# B21DCDT245_05.net
KiCad netlist of a schematic drawn in Altium Designer
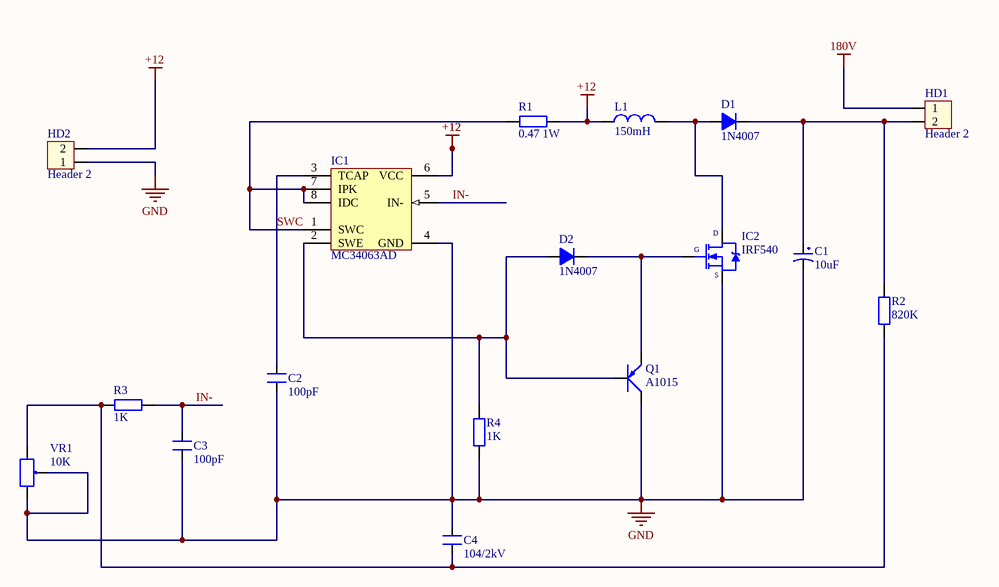
[diagram p0: B21DCDT245_05.SchDoc]

(export (version "E")
  (design (tool "Eeschema 10.0.6"))
  (components
    (comp (ref "C1")
      (value "10uF")
      (footprint "CP1/2")
      (description "Cap P  0,1uF < 22uF , 16 - 50V")
      (libsource (lib "Devzone_SCHLib") (part "CP1"))
    )
    (comp (ref "C2")
      (value "100pF")
      (footprint "CN1")
      (description "Cap np  1pF - 472pF")
      (libsource (lib "syhaunguyen") (part "CN1"))
    )
    (comp (ref "C3")
      (value "100pF")
      (footprint "CN1")
      (description "Cap np  1pF - 472pF")
      (libsource (lib "syhaunguyen") (part "CN1"))
    )
    (comp (ref "C4")
      (value "104/2kV")
      (footprint "CN1")
      (description "Cap np  1pF - 472pF")
      (libsource (lib "syhaunguyen") (part "CN1"))
    )
    (comp (ref "D1")
      (value "1N4007")
      (footprint "D1A")
      (description "Diode 1A")
      (libsource (lib "syhaunguyen") (part "D1A"))
    )
    (comp (ref "D2")
      (value "1N4007")
      (footprint "D1A")
      (description "Diode 1A")
      (libsource (lib "syhaunguyen") (part "D1A"))
    )
    (comp (ref "HD1")
      (value "Header 2")
      (footprint "HED2")
      (description "Header 2 (Green)")
      (libsource (lib "") (part "Hed2_1"))
    )
    (comp (ref "HD2")
      (value "Header 2")
      (footprint "HED2")
      (description "Header 2 (Green)")
      (libsource (lib "Devzone_SCHLib") (part "Hed2"))
    )
    (comp (ref "IC1")
      (value "MC34063AD")
      (footprint "DIP8")
      (description "DC-to-DC Converter Control Circuit")
      (fields (field (name "PUBLISHER") "Altium Limited"))
      (libsource (lib "Devzone_SCHLib") (part "MC34063AD"))
    )
    (comp (ref "IC2")
      (value "IRF540")
      (footprint "QTO220 - FLAT")
      (libsource (lib "My library altium") (part "IRF540"))
    )
    (comp (ref "L1")
      (value "150mH")
      (footprint "L/0.4")
      (description "Inductor")
      (libsource (lib "syhaunguyen") (part "L1"))
    )
    (comp (ref "Q1")
      (value "A1015")
      (footprint "QTO-92")
      (description "PNP 600mW, ECB")
      (libsource (lib "Devzone_SCHLib") (part "A1015"))
    )
    (comp (ref "R1")
      (value "0.47 1W")
      (footprint "VioletofSun:SM-1206")
      (description "Resistor SMD")
      (libsource (lib "VioletofSun") (part "RM"))
    )
    (comp (ref "R2")
      (value "820K")
      (footprint "VioletofSun:SM-1206")
      (description "Resistor SMD")
      (libsource (lib "VioletofSun") (part "RM"))
    )
    (comp (ref "R3")
      (value "1K")
      (footprint "VioletofSun:SM-1206")
      (description "Resistor SMD")
      (libsource (lib "VioletofSun") (part "RM"))
    )
    (comp (ref "R4")
      (value "1K")
      (footprint "VioletofSun:SM-1206")
      (description "Resistor SMD")
      (libsource (lib "VioletofSun") (part "RM"))
    )
    (comp (ref "VR1")
      (value "10K")
      (footprint "VR")
      (description "Var Resistor")
      (libsource (lib "syhaunguyen") (part "VR"))
    )
  )
  (nets
    (net (code "1") (name "+12") (class "Default")
      (node (ref "HD2") (pin "2") (pinfunction "2_2") (pintype "passive"))
      (node (ref "IC1") (pin "6") (pinfunction "VCC_6") (pintype "power_in"))
      (node (ref "L1") (pin "1") (pinfunction "1_1") (pintype "passive"))
      (node (ref "R1") (pin "1") (pinfunction "1_1") (pintype "passive"))
    )
    (net (code "2") (name "/IN-") (class "Default")
      (node (ref "C3") (pin "2") (pinfunction "2_2") (pintype "passive"))
      (node (ref "IC1") (pin "5") (pinfunction "IN-_5") (pintype "input"))
      (node (ref "R3") (pin "2") (pinfunction "2_2") (pintype "passive"))
    )
    (net (code "3") (name "/SWC") (class "Default")
      (node (ref "C2") (pin "2") (pinfunction "2_2") (pintype "passive"))
      (node (ref "IC1") (pin "1") (pinfunction "SWC_1") (pintype "passive"))
      (node (ref "IC1") (pin "3") (pinfunction "TCAP_3") (pintype "passive"))
      (node (ref "IC1") (pin "7") (pinfunction "IPK_7") (pintype "passive"))
      (node (ref "IC1") (pin "8") (pinfunction "IDC_8") (pintype "open_collector"))
      (node (ref "R1") (pin "2") (pinfunction "2_2") (pintype "passive"))
    )
    (net (code "4") (name "180V") (class "Default")
      (node (ref "HD1") (pin "1") (pinfunction "1_1") (pintype "passive"))
    )
    (net (code "5") (name "GND") (class "Default")
      (node (ref "C1") (pin "2") (pinfunction "2_2") (pintype "passive"))
      (node (ref "C2") (pin "1") (pinfunction "1_1") (pintype "passive"))
      (node (ref "C3") (pin "1") (pinfunction "1_1") (pintype "passive"))
      (node (ref "C4") (pin "2") (pinfunction "2_2") (pintype "passive"))
      (node (ref "HD2") (pin "1") (pinfunction "1_1") (pintype "passive"))
      (node (ref "IC1") (pin "4") (pinfunction "GND_4") (pintype "power_in"))
      (node (ref "IC2") (pin "3") (pinfunction "S_3") (pintype "passive"))
      (node (ref "Q1") (pin "2") (pinfunction "C_2") (pintype "passive"))
      (node (ref "R4") (pin "2") (pinfunction "2_2") (pintype "passive"))
      (node (ref "VR1") (pin "2") (pinfunction "2_2") (pintype "passive"))
      (node (ref "VR1") (pin "3") (pinfunction "3_3") (pintype "passive"))
    )
    (net (code "6") (name "Net-(C4-Pad1)") (class "Default")
      (node (ref "C4") (pin "1") (pinfunction "1_1") (pintype "passive"))
      (node (ref "R2") (pin "2") (pinfunction "2_2") (pintype "passive"))
      (node (ref "R3") (pin "1") (pinfunction "1_1") (pintype "passive"))
      (node (ref "VR1") (pin "1") (pinfunction "1_1") (pintype "passive"))
    )
    (net (code "7") (name "Net-(D1-A)") (class "Default")
      (node (ref "D1") (pin "1") (pinfunction "A_1") (pintype "passive"))
      (node (ref "IC2") (pin "2") (pinfunction "D_2") (pintype "passive"))
      (node (ref "L1") (pin "2") (pinfunction "2_2") (pintype "passive"))
    )
    (net (code "8") (name "Net-(D1-K)") (class "Default")
      (node (ref "C1") (pin "1") (pinfunction "1_1") (pintype "passive"))
      (node (ref "D1") (pin "2") (pinfunction "K_2") (pintype "passive"))
      (node (ref "HD1") (pin "2") (pinfunction "2_2") (pintype "passive"))
      (node (ref "R2") (pin "1") (pinfunction "1_1") (pintype "passive"))
    )
    (net (code "9") (name "Net-(D2-A)") (class "Default")
      (node (ref "D2") (pin "1") (pinfunction "A_1") (pintype "passive"))
      (node (ref "IC1") (pin "2") (pinfunction "SWE_2") (pintype "passive"))
      (node (ref "Q1") (pin "3") (pinfunction "B_3") (pintype "passive"))
      (node (ref "R4") (pin "1") (pinfunction "1_1") (pintype "passive"))
    )
    (net (code "10") (name "Net-(D2-K)") (class "Default")
      (node (ref "D2") (pin "2") (pinfunction "K_2") (pintype "passive"))
      (node (ref "IC2") (pin "1") (pinfunction "G_1") (pintype "passive"))
      (node (ref "Q1") (pin "1") (pinfunction "E_1") (pintype "passive"))
    )
  )
)
